# 5_Volts_and_3_3_Volts_Power_Supply.net
KiCad netlist of a schematic drawn in Altium Designer
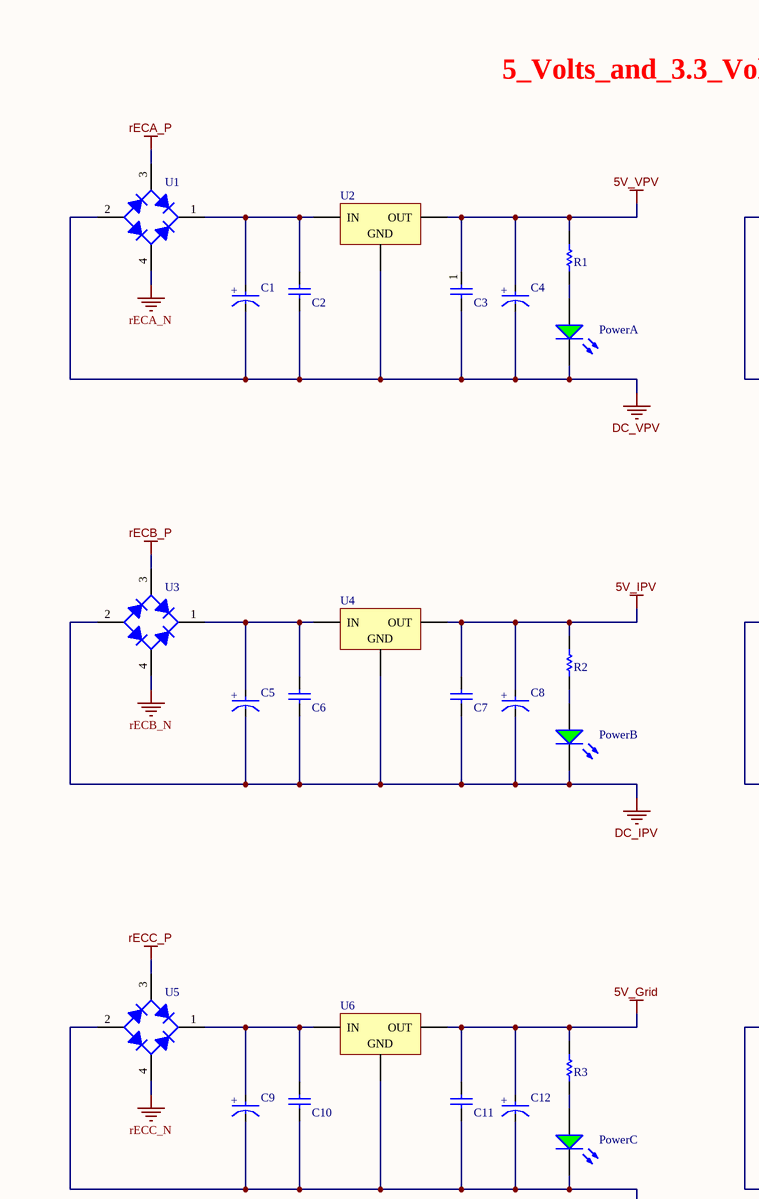
[diagram p0: 5_Volts_and_3.3_Volts_Power_Supply.SchDoc, top left]
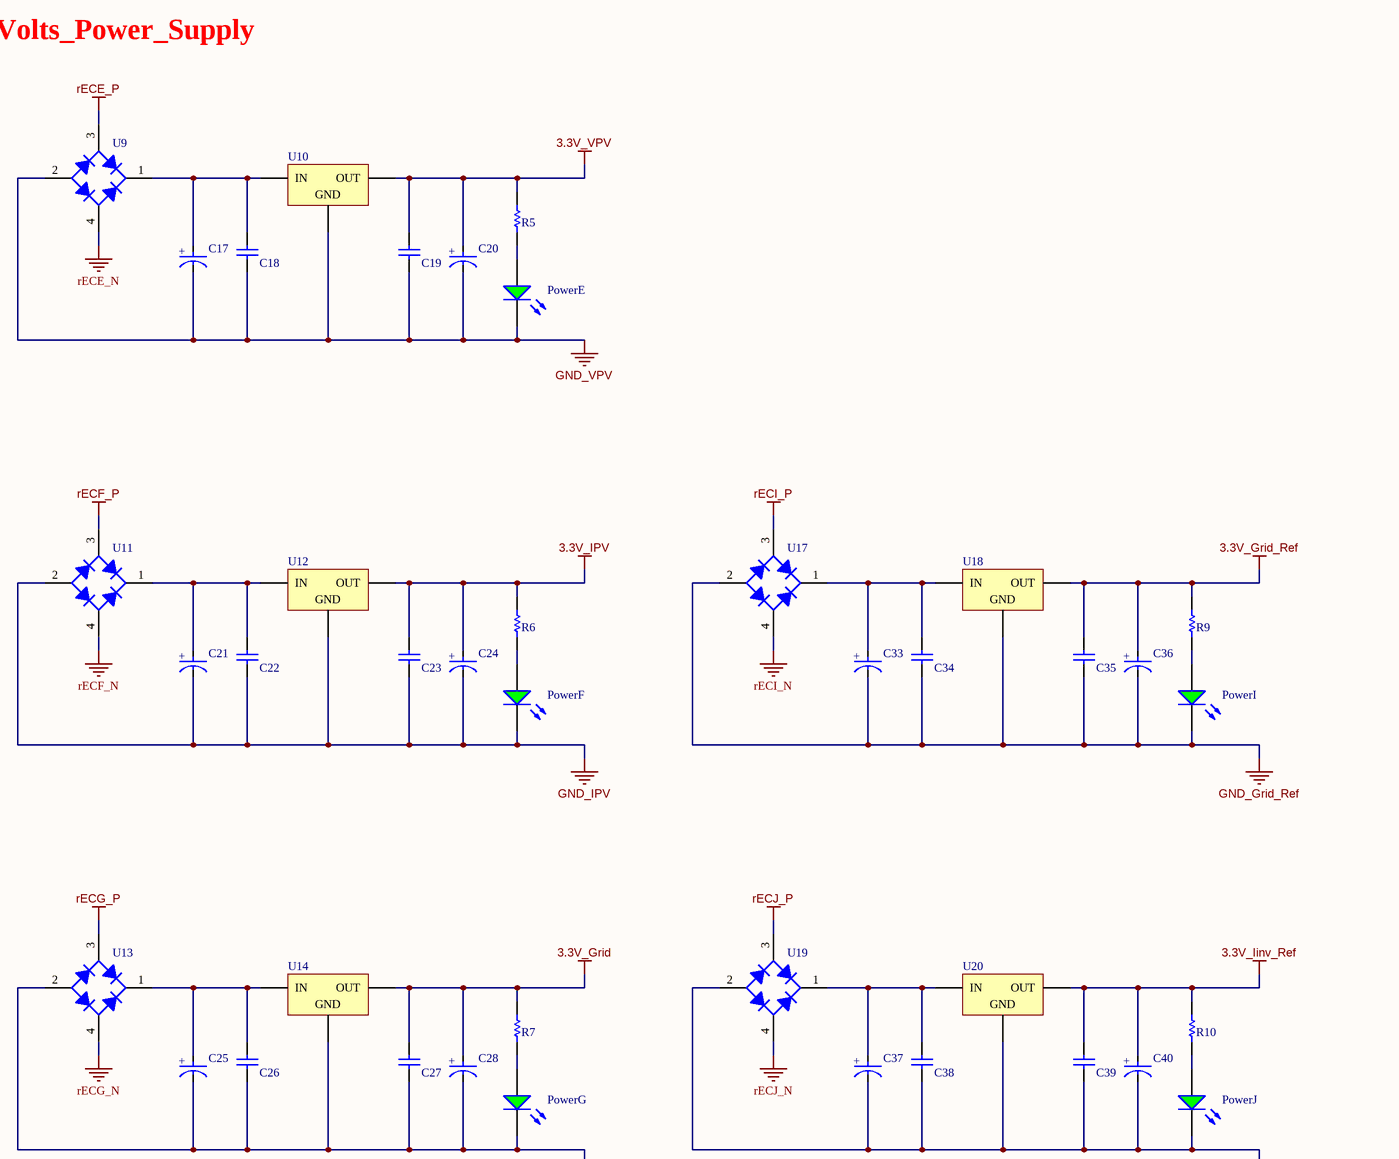
[diagram p1: 5_Volts_and_3.3_Volts_Power_Supply.SchDoc, top right]
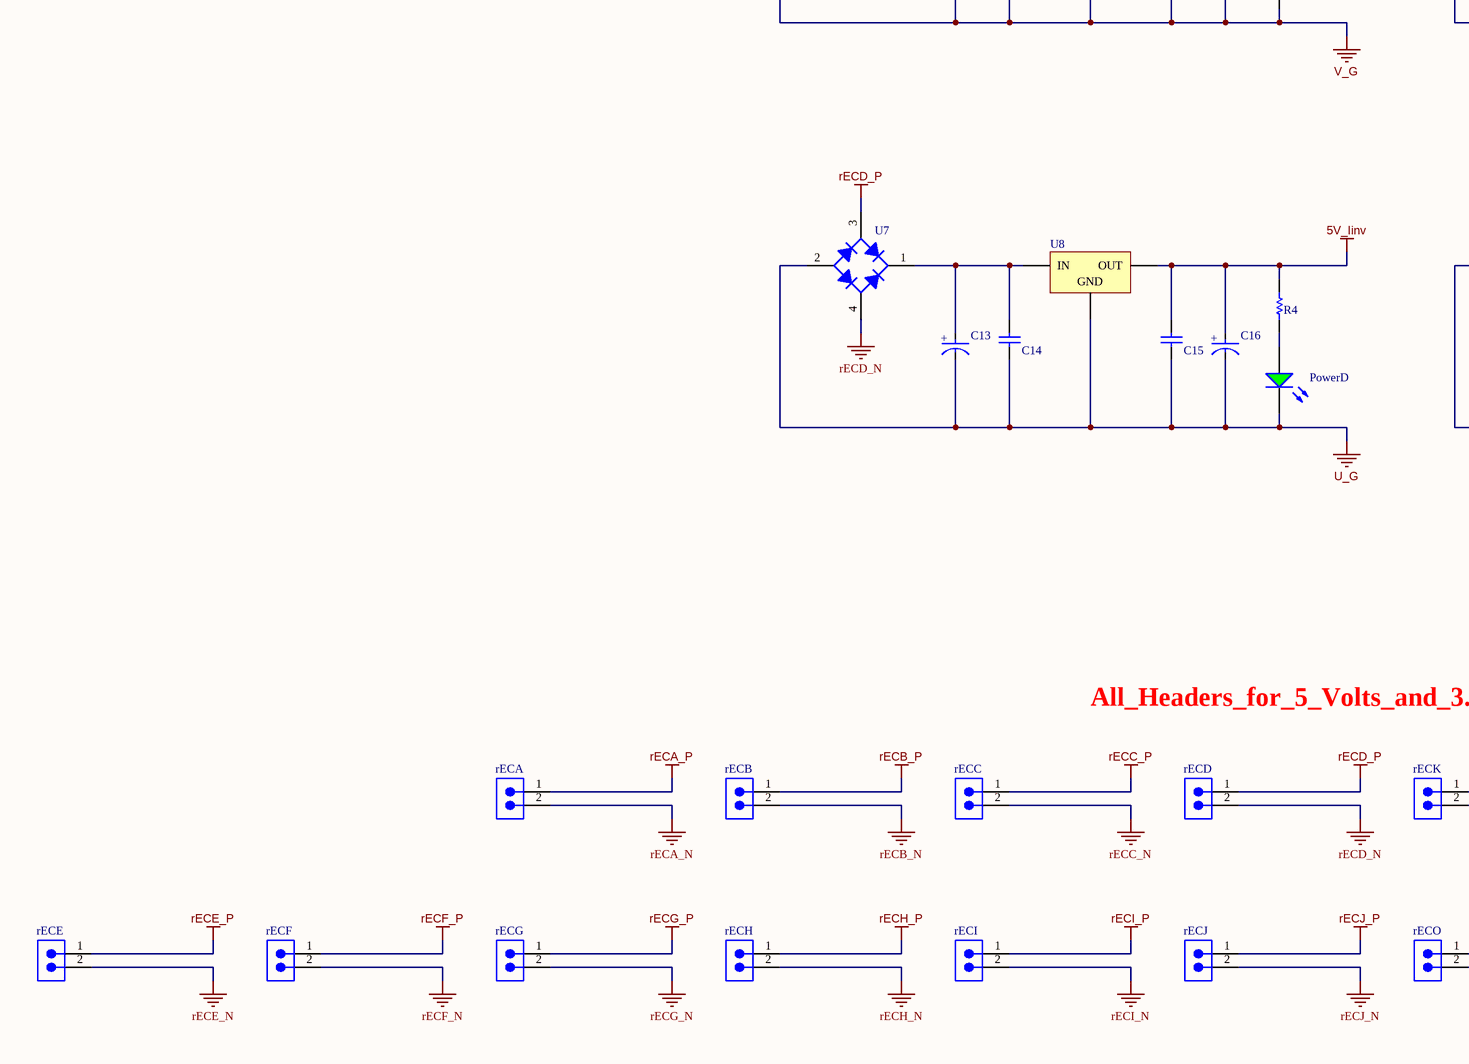
[diagram p2: 5_Volts_and_3.3_Volts_Power_Supply.SchDoc, bottom left]
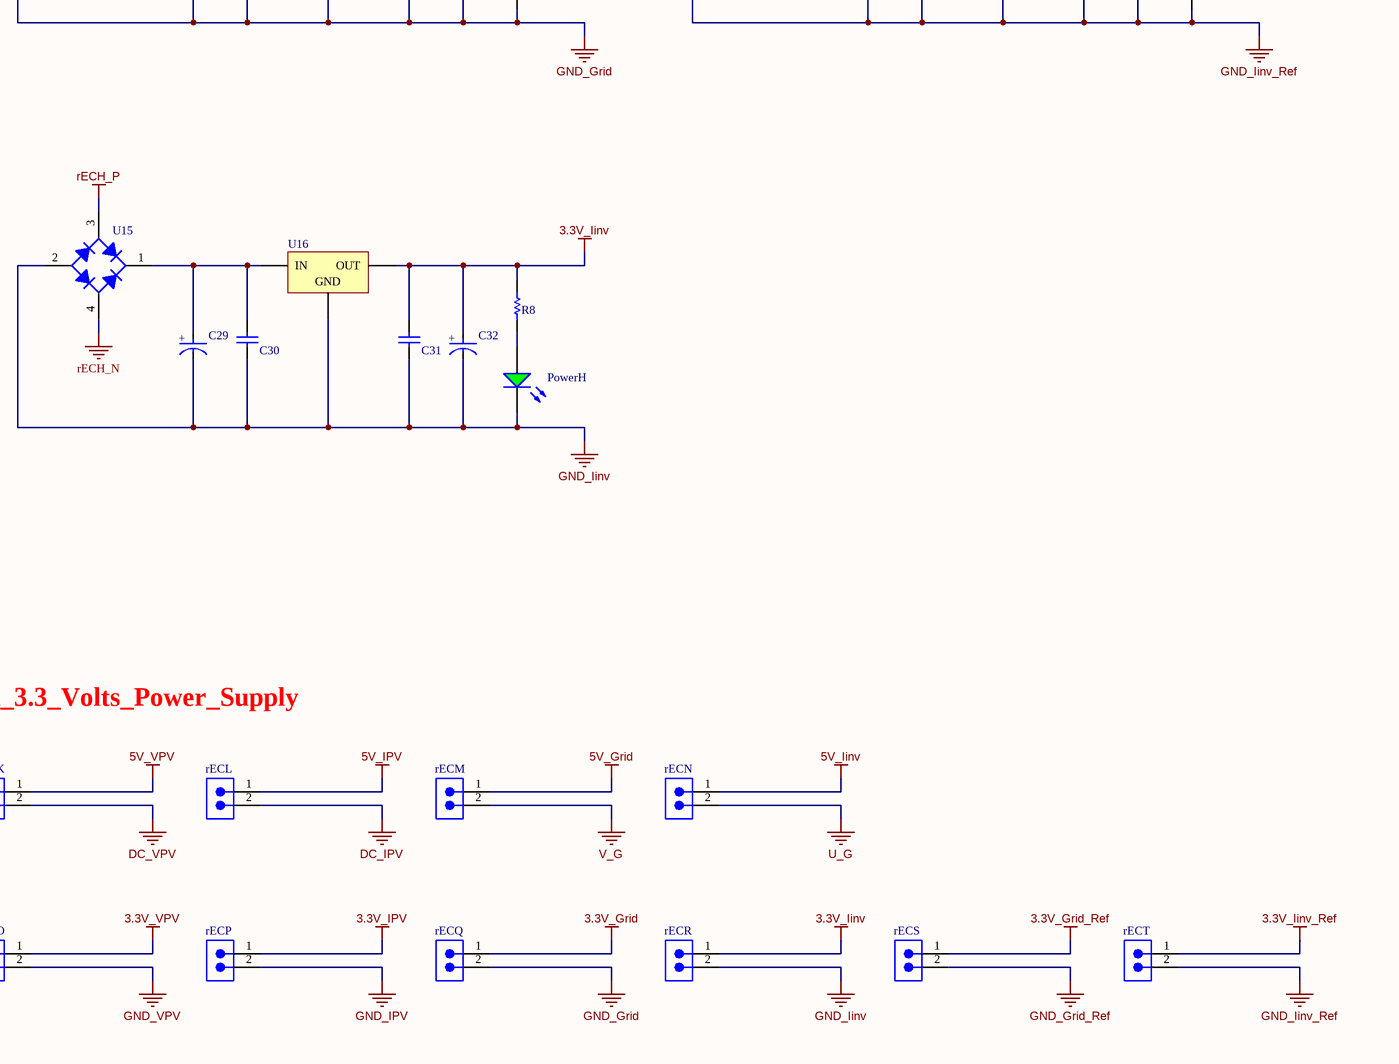
[diagram p3: 5_Volts_and_3.3_Volts_Power_Supply.SchDoc, bottom right]

(export (version "E")
  (design (tool "Eeschema 10.0.6"))
  (components
    (comp (ref "C1")
      (value "EEE-FK1H471AM")
      (footprint "FP-FKJ16-MFG")
      (description "CAP ALUM 470UF 20% 50V SMD")
      (fields (field (name "VOLTAGE") "50V") (field (name "TOLERANCE") "20%"))
      (libsource (lib "Altium Content Vault") (part "a00bbbee19879c290e62620ae7e47b1"))
    )
    (comp (ref "C2")
      (value "GRM219R71H334KA88D")
      (footprint "CAPC2013X95X45ML10T25")
      (description "Multilayer Ceramic Capacitor, 0.33 uF, 50 V, ï¿½ 10%, X7R, 0805 [2012 Metric]")
      (fields (field (name "MANUFACTURER") "Murata"))
      (libsource (lib "Altium Content Vault") (part "CAP"))
    )
    (comp (ref "C3")
      (value "GRM21BR71H104KA01L")
      (footprint "CAPC2013X135X45ML10T25")
      (description "Chip Capacitor, 0.1 uF, +/- 10%, 50 V, -55 to 125 degC, 0805 (2012 Metric), RoHS, Tape and Reel")
      (fields (field (name "VOLTAGE") "50V") (field (name "TOLERANCE") "10%"))
      (libsource (lib "") (part "CAP-NP-2_1"))
    )
    (comp (ref "C4")
      (value "EEE-FK1H100UR")
      (footprint "FP-FKC-MFG")
      (description "CAP ALUM 10UF 20% 50V SMD")
      (fields (field (name "TOLERANCE") "20%") (field (name "VOLTAGE") "50V"))
      (libsource (lib "Altium Content Vault") (part "a00bbbee19879c290e62620ae7e47b1"))
    )
    (comp (ref "C5")
      (value "EEE-FK1H471AM")
      (footprint "FP-FKJ16-MFG")
      (description "CAP ALUM 470UF 20% 50V SMD")
      (fields (field (name "VOLTAGE") "50V") (field (name "TOLERANCE") "20%"))
      (libsource (lib "Altium Content Vault") (part "a00bbbee19879c290e62620ae7e47b1"))
    )
    (comp (ref "C6")
      (value "GRM219R71H334KA88D")
      (footprint "CAPC2013X95X45ML10T25")
      (description "Multilayer Ceramic Capacitor, 0.33 uF, 50 V, ï¿½ 10%, X7R, 0805 [2012 Metric]")
      (fields (field (name "MANUFACTURER") "Murata"))
      (libsource (lib "Altium Content Vault") (part "CAP"))
    )
    (comp (ref "C7")
      (value "GRM21BR71H104KA01L")
      (footprint "CAPC2013X135X45ML10T25")
      (description "Chip Capacitor, 0.1 uF, +/- 10%, 50 V, -55 to 125 degC, 0805 (2012 Metric), RoHS, Tape and Reel")
      (fields (field (name "VOLTAGE") "50V") (field (name "TOLERANCE") "10%"))
      (libsource (lib "Altium Content Vault") (part "CAP-NP-2"))
    )
    (comp (ref "C8")
      (value "EEE-FK1H100UR")
      (footprint "FP-FKC-MFG")
      (description "CAP ALUM 10UF 20% 50V SMD")
      (fields (field (name "TOLERANCE") "20%") (field (name "VOLTAGE") "50V"))
      (libsource (lib "Altium Content Vault") (part "a00bbbee19879c290e62620ae7e47b1"))
    )
    (comp (ref "C9")
      (value "EEE-FK1H471AM")
      (footprint "FP-FKJ16-MFG")
      (description "CAP ALUM 470UF 20% 50V SMD")
      (fields (field (name "VOLTAGE") "50V") (field (name "TOLERANCE") "20%"))
      (libsource (lib "Altium Content Vault") (part "a00bbbee19879c290e62620ae7e47b1"))
    )
    (comp (ref "C10")
      (value "GRM219R71H334KA88D")
      (footprint "CAPC2013X95X45ML10T25")
      (description "Multilayer Ceramic Capacitor, 0.33 uF, 50 V, ï¿½ 10%, X7R, 0805 [2012 Metric]")
      (fields (field (name "MANUFACTURER") "Murata"))
      (libsource (lib "Altium Content Vault") (part "CAP"))
    )
    (comp (ref "C11")
      (value "GRM21BR71H104KA01L")
      (footprint "CAPC2013X135X45ML10T25")
      (description "Chip Capacitor, 0.1 uF, +/- 10%, 50 V, -55 to 125 degC, 0805 (2012 Metric), RoHS, Tape and Reel")
      (fields (field (name "VOLTAGE") "50V") (field (name "TOLERANCE") "10%"))
      (libsource (lib "Altium Content Vault") (part "CAP-NP-2"))
    )
    (comp (ref "C12")
      (value "EEE-FK1H100UR")
      (footprint "FP-FKC-MFG")
      (description "CAP ALUM 10UF 20% 50V SMD")
      (fields (field (name "TOLERANCE") "20%") (field (name "VOLTAGE") "50V"))
      (libsource (lib "Altium Content Vault") (part "a00bbbee19879c290e62620ae7e47b1"))
    )
    (comp (ref "C13")
      (value "EEE-FK1H471AM")
      (footprint "FP-FKJ16-MFG")
      (description "CAP ALUM 470UF 20% 50V SMD")
      (fields (field (name "VOLTAGE") "50V") (field (name "TOLERANCE") "20%"))
      (libsource (lib "Altium Content Vault") (part "a00bbbee19879c290e62620ae7e47b1"))
    )
    (comp (ref "C14")
      (value "GRM219R71H334KA88D")
      (footprint "CAPC2013X95X45ML10T25")
      (description "Multilayer Ceramic Capacitor, 0.33 uF, 50 V, ï¿½ 10%, X7R, 0805 [2012 Metric]")
      (fields (field (name "MANUFACTURER") "Murata"))
      (libsource (lib "Altium Content Vault") (part "CAP"))
    )
    (comp (ref "C15")
      (value "GRM21BR71H104KA01L")
      (footprint "CAPC2013X135X45ML10T25")
      (description "Chip Capacitor, 0.1 uF, +/- 10%, 50 V, -55 to 125 degC, 0805 (2012 Metric), RoHS, Tape and Reel")
      (fields (field (name "VOLTAGE") "50V") (field (name "TOLERANCE") "10%"))
      (libsource (lib "Altium Content Vault") (part "CAP-NP-2"))
    )
    (comp (ref "C16")
      (value "EEE-FK1H100UR")
      (footprint "FP-FKC-MFG")
      (description "CAP ALUM 10UF 20% 50V SMD")
      (fields (field (name "TOLERANCE") "20%") (field (name "VOLTAGE") "50V"))
      (libsource (lib "Altium Content Vault") (part "a00bbbee19879c290e62620ae7e47b1"))
    )
    (comp (ref "C17")
      (value "EEE-FK1H471AM")
      (footprint "FP-FKJ16-MFG")
      (description "CAP ALUM 470UF 20% 50V SMD")
      (fields (field (name "VOLTAGE") "50V") (field (name "TOLERANCE") "20%"))
      (libsource (lib "Altium Content Vault") (part "a00bbbee19879c290e62620ae7e47b1"))
    )
    (comp (ref "C18")
      (value "GRM219R71H334KA88D")
      (footprint "CAPC2013X95X45ML10T25")
      (description "Multilayer Ceramic Capacitor, 0.33 uF, 50 V, ï¿½ 10%, X7R, 0805 [2012 Metric]")
      (fields (field (name "MANUFACTURER") "Murata"))
      (libsource (lib "Altium Content Vault") (part "CAP"))
    )
    (comp (ref "C19")
      (value "GRM21BR71H104KA01L")
      (footprint "CAPC2013X135X45ML10T25")
      (description "Chip Capacitor, 0.1 uF, +/- 10%, 50 V, -55 to 125 degC, 0805 (2012 Metric), RoHS, Tape and Reel")
      (fields (field (name "VOLTAGE") "50V") (field (name "TOLERANCE") "10%"))
      (libsource (lib "Altium Content Vault") (part "CAP-NP-2"))
    )
    (comp (ref "C20")
      (value "EEE-FK1H100UR")
      (footprint "FP-FKC-MFG")
      (description "CAP ALUM 10UF 20% 50V SMD")
      (fields (field (name "TOLERANCE") "20%") (field (name "VOLTAGE") "50V"))
      (libsource (lib "Altium Content Vault") (part "a00bbbee19879c290e62620ae7e47b1"))
    )
    (comp (ref "C21")
      (value "EEE-FK1H471AM")
      (footprint "FP-FKJ16-MFG")
      (description "CAP ALUM 470UF 20% 50V SMD")
      (fields (field (name "VOLTAGE") "50V") (field (name "TOLERANCE") "20%"))
      (libsource (lib "Altium Content Vault") (part "a00bbbee19879c290e62620ae7e47b1"))
    )
    (comp (ref "C22")
      (value "GRM219R71H334KA88D")
      (footprint "CAPC2013X95X45ML10T25")
      (description "Multilayer Ceramic Capacitor, 0.33 uF, 50 V, ï¿½ 10%, X7R, 0805 [2012 Metric]")
      (fields (field (name "MANUFACTURER") "Murata"))
      (libsource (lib "Altium Content Vault") (part "CAP"))
    )
    (comp (ref "C23")
      (value "GRM21BR71H104KA01L")
      (footprint "CAPC2013X135X45ML10T25")
      (description "Chip Capacitor, 0.1 uF, +/- 10%, 50 V, -55 to 125 degC, 0805 (2012 Metric), RoHS, Tape and Reel")
      (fields (field (name "VOLTAGE") "50V") (field (name "TOLERANCE") "10%"))
      (libsource (lib "Altium Content Vault") (part "CAP-NP-2"))
    )
    (comp (ref "C24")
      (value "EEE-FK1H100UR")
      (footprint "FP-FKC-MFG")
      (description "CAP ALUM 10UF 20% 50V SMD")
      (fields (field (name "TOLERANCE") "20%") (field (name "VOLTAGE") "50V"))
      (libsource (lib "Altium Content Vault") (part "a00bbbee19879c290e62620ae7e47b1"))
    )
    (comp (ref "C25")
      (value "EEE-FK1H471AM")
      (footprint "FP-FKJ16-MFG")
      (description "CAP ALUM 470UF 20% 50V SMD")
      (fields (field (name "VOLTAGE") "50V") (field (name "TOLERANCE") "20%"))
      (libsource (lib "Altium Content Vault") (part "a00bbbee19879c290e62620ae7e47b1"))
    )
    (comp (ref "C26")
      (value "GRM219R71H334KA88D")
      (footprint "CAPC2013X95X45ML10T25")
      (description "Multilayer Ceramic Capacitor, 0.33 uF, 50 V, ï¿½ 10%, X7R, 0805 [2012 Metric]")
      (fields (field (name "MANUFACTURER") "Murata"))
      (libsource (lib "Altium Content Vault") (part "CAP"))
    )
    (comp (ref "C27")
      (value "GRM21BR71H104KA01L")
      (footprint "CAPC2013X135X45ML10T25")
      (description "Chip Capacitor, 0.1 uF, +/- 10%, 50 V, -55 to 125 degC, 0805 (2012 Metric), RoHS, Tape and Reel")
      (fields (field (name "VOLTAGE") "50V") (field (name "TOLERANCE") "10%"))
      (libsource (lib "Altium Content Vault") (part "CAP-NP-2"))
    )
    (comp (ref "C28")
      (value "EEE-FK1H100UR")
      (footprint "FP-FKC-MFG")
      (description "CAP ALUM 10UF 20% 50V SMD")
      (fields (field (name "TOLERANCE") "20%") (field (name "VOLTAGE") "50V"))
      (libsource (lib "Altium Content Vault") (part "a00bbbee19879c290e62620ae7e47b1"))
    )
    (comp (ref "C29")
      (value "EEE-FK1H471AM")
      (footprint "FP-FKJ16-MFG")
      (description "CAP ALUM 470UF 20% 50V SMD")
      (fields (field (name "VOLTAGE") "50V") (field (name "TOLERANCE") "20%"))
      (libsource (lib "Altium Content Vault") (part "a00bbbee19879c290e62620ae7e47b1"))
    )
    (comp (ref "C30")
      (value "GRM219R71H334KA88D")
      (footprint "CAPC2013X95X45ML10T25")
      (description "Multilayer Ceramic Capacitor, 0.33 uF, 50 V, ï¿½ 10%, X7R, 0805 [2012 Metric]")
      (fields (field (name "MANUFACTURER") "Murata"))
      (libsource (lib "Altium Content Vault") (part "CAP"))
    )
    (comp (ref "C31")
      (value "GRM21BR71H104KA01L")
      (footprint "CAPC2013X135X45ML10T25")
      (description "Chip Capacitor, 0.1 uF, +/- 10%, 50 V, -55 to 125 degC, 0805 (2012 Metric), RoHS, Tape and Reel")
      (fields (field (name "VOLTAGE") "50V") (field (name "TOLERANCE") "10%"))
      (libsource (lib "Altium Content Vault") (part "CAP-NP-2"))
    )
    (comp (ref "C32")
      (value "EEE-FK1H100UR")
      (footprint "FP-FKC-MFG")
      (description "CAP ALUM 10UF 20% 50V SMD")
      (fields (field (name "TOLERANCE") "20%") (field (name "VOLTAGE") "50V"))
      (libsource (lib "Altium Content Vault") (part "a00bbbee19879c290e62620ae7e47b1"))
    )
    (comp (ref "C33")
      (value "EEE-FK1H471AM")
      (footprint "FP-FKJ16-MFG")
      (description "CAP ALUM 470UF 20% 50V SMD")
      (fields (field (name "VOLTAGE") "50V") (field (name "TOLERANCE") "20%"))
      (libsource (lib "Altium Content Vault") (part "a00bbbee19879c290e62620ae7e47b1"))
    )
    (comp (ref "C34")
      (value "GRM219R71H334KA88D")
      (footprint "CAPC2013X95X45ML10T25")
      (description "Multilayer Ceramic Capacitor, 0.33 uF, 50 V, ï¿½ 10%, X7R, 0805 [2012 Metric]")
      (fields (field (name "MANUFACTURER") "Murata"))
      (libsource (lib "Altium Content Vault") (part "CAP"))
    )
    (comp (ref "C35")
      (value "GRM21BR71H104KA01L")
      (footprint "CAPC2013X135X45ML10T25")
      (description "Chip Capacitor, 0.1 uF, +/- 10%, 50 V, -55 to 125 degC, 0805 (2012 Metric), RoHS, Tape and Reel")
      (fields (field (name "VOLTAGE") "50V") (field (name "TOLERANCE") "10%"))
      (libsource (lib "Altium Content Vault") (part "CAP-NP-2"))
    )
    (comp (ref "C36")
      (value "EEE-FK1H100UR")
      (footprint "FP-FKC-MFG")
      (description "CAP ALUM 10UF 20% 50V SMD")
      (fields (field (name "TOLERANCE") "20%") (field (name "VOLTAGE") "50V"))
      (libsource (lib "Altium Content Vault") (part "a00bbbee19879c290e62620ae7e47b1"))
    )
    (comp (ref "C37")
      (value "EEE-FK1H471AM")
      (footprint "FP-FKJ16-MFG")
      (description "CAP ALUM 470UF 20% 50V SMD")
      (fields (field (name "VOLTAGE") "50V") (field (name "TOLERANCE") "20%"))
      (libsource (lib "Altium Content Vault") (part "a00bbbee19879c290e62620ae7e47b1"))
    )
    (comp (ref "C38")
      (value "GRM219R71H334KA88D")
      (footprint "CAPC2013X95X45ML10T25")
      (description "Multilayer Ceramic Capacitor, 0.33 uF, 50 V, ï¿½ 10%, X7R, 0805 [2012 Metric]")
      (fields (field (name "MANUFACTURER") "Murata"))
      (libsource (lib "Altium Content Vault") (part "CAP"))
    )
    (comp (ref "C39")
      (value "GRM21BR71H104KA01L")
      (footprint "CAPC2013X135X45ML10T25")
      (description "Chip Capacitor, 0.1 uF, +/- 10%, 50 V, -55 to 125 degC, 0805 (2012 Metric), RoHS, Tape and Reel")
      (fields (field (name "VOLTAGE") "50V") (field (name "TOLERANCE") "10%"))
      (libsource (lib "Altium Content Vault") (part "CAP-NP-2"))
    )
    (comp (ref "C40")
      (value "EEE-FK1H100UR")
      (footprint "FP-FKC-MFG")
      (description "CAP ALUM 10UF 20% 50V SMD")
      (fields (field (name "TOLERANCE") "20%") (field (name "VOLTAGE") "50V"))
      (libsource (lib "Altium Content Vault") (part "a00bbbee19879c290e62620ae7e47b1"))
    )
    (comp (ref "PowerA")
      (value "150080GS75000")
      (footprint "WL-SMCW_0805_150080xx75000")
      (description "WURTH ELEKTRONIK - 150080GS75000 - LED, Green, SMD, 0805, 30 mA, 3.2 V, 520 nm")
      (libsource (lib "Altium Content Vault") (part "LED_Green_2A-1K"))
    )
    (comp (ref "PowerB")
      (value "150080GS75000")
      (footprint "WL-SMCW_0805_150080xx75000")
      (description "WURTH ELEKTRONIK - 150080GS75000 - LED, Green, SMD, 0805, 30 mA, 3.2 V, 520 nm")
      (libsource (lib "Altium Content Vault") (part "LED_Green_2A-1K"))
    )
    (comp (ref "PowerC")
      (value "150080GS75000")
      (footprint "WL-SMCW_0805_150080xx75000")
      (description "WURTH ELEKTRONIK - 150080GS75000 - LED, Green, SMD, 0805, 30 mA, 3.2 V, 520 nm")
      (libsource (lib "Altium Content Vault") (part "LED_Green_2A-1K"))
    )
    (comp (ref "PowerD")
      (value "150080GS75000")
      (footprint "WL-SMCW_0805_150080xx75000")
      (description "WURTH ELEKTRONIK - 150080GS75000 - LED, Green, SMD, 0805, 30 mA, 3.2 V, 520 nm")
      (libsource (lib "Altium Content Vault") (part "LED_Green_2A-1K"))
    )
    (comp (ref "PowerE")
      (value "150080GS75000")
      (footprint "WL-SMCW_0805_150080xx75000")
      (description "WURTH ELEKTRONIK - 150080GS75000 - LED, Green, SMD, 0805, 30 mA, 3.2 V, 520 nm")
      (libsource (lib "Altium Content Vault") (part "LED_Green_2A-1K"))
    )
    (comp (ref "PowerF")
      (value "150080GS75000")
      (footprint "WL-SMCW_0805_150080xx75000")
      (description "WURTH ELEKTRONIK - 150080GS75000 - LED, Green, SMD, 0805, 30 mA, 3.2 V, 520 nm")
      (libsource (lib "Altium Content Vault") (part "LED_Green_2A-1K"))
    )
    (comp (ref "PowerG")
      (value "150080GS75000")
      (footprint "WL-SMCW_0805_150080xx75000")
      (description "WURTH ELEKTRONIK - 150080GS75000 - LED, Green, SMD, 0805, 30 mA, 3.2 V, 520 nm")
      (libsource (lib "Altium Content Vault") (part "LED_Green_2A-1K"))
    )
    (comp (ref "PowerH")
      (value "150080GS75000")
      (footprint "WL-SMCW_0805_150080xx75000")
      (description "WURTH ELEKTRONIK - 150080GS75000 - LED, Green, SMD, 0805, 30 mA, 3.2 V, 520 nm")
      (libsource (lib "Altium Content Vault") (part "LED_Green_2A-1K"))
    )
    (comp (ref "PowerI")
      (value "150080GS75000")
      (footprint "WL-SMCW_0805_150080xx75000")
      (description "WURTH ELEKTRONIK - 150080GS75000 - LED, Green, SMD, 0805, 30 mA, 3.2 V, 520 nm")
      (libsource (lib "Altium Content Vault") (part "LED_Green_2A-1K"))
    )
    (comp (ref "PowerJ")
      (value "150080GS75000")
      (footprint "WL-SMCW_0805_150080xx75000")
      (description "WURTH ELEKTRONIK - 150080GS75000 - LED, Green, SMD, 0805, 30 mA, 3.2 V, 520 nm")
      (libsource (lib "Altium Content Vault") (part "LED_Green_2A-1K"))
    )
    (comp (ref "R1")
      (value "ERJ-6ENF1001V")
      (footprint "RESC2013X70X40ML20T20")
      (description "Chip Resistor, 1 KOhm, +/- 1%, 0.125 W, -55 to 155 degC, 0805 (2012 Metric), RoHS, Tape and Reel")
      (fields (field (name "MANUFACTURER") "Panasonic"))
      (libsource (lib "Altium Content Vault") (part "RES-2"))
    )
    (comp (ref "R2")
      (value "ERJ-6ENF1001V")
      (footprint "RESC2013X70X40ML20T20")
      (description "Chip Resistor, 1 KOhm, +/- 1%, 0.125 W, -55 to 155 degC, 0805 (2012 Metric), RoHS, Tape and Reel")
      (fields (field (name "MANUFACTURER") "Panasonic"))
      (libsource (lib "Altium Content Vault") (part "RES-2"))
    )
    (comp (ref "R3")
      (value "ERJ-6ENF1001V")
      (footprint "RESC2013X70X40ML20T20")
      (description "Chip Resistor, 1 KOhm, +/- 1%, 0.125 W, -55 to 155 degC, 0805 (2012 Metric), RoHS, Tape and Reel")
      (fields (field (name "MANUFACTURER") "Panasonic"))
      (libsource (lib "Altium Content Vault") (part "RES-2"))
    )
    (comp (ref "R4")
      (value "ERJ-6ENF1001V")
      (footprint "RESC2013X70X40ML20T20")
      (description "Chip Resistor, 1 KOhm, +/- 1%, 0.125 W, -55 to 155 degC, 0805 (2012 Metric), RoHS, Tape and Reel")
      (fields (field (name "MANUFACTURER") "Panasonic"))
      (libsource (lib "Altium Content Vault") (part "RES-2"))
    )
    (comp (ref "R5")
      (value "ERJ-6ENF1001V")
      (footprint "RESC2013X70X40ML20T20")
      (description "Chip Resistor, 1 KOhm, +/- 1%, 0.125 W, -55 to 155 degC, 0805 (2012 Metric), RoHS, Tape and Reel")
      (fields (field (name "MANUFACTURER") "Panasonic"))
      (libsource (lib "Altium Content Vault") (part "RES-2"))
    )
    (comp (ref "R6")
      (value "ERJ-6ENF1001V")
      (footprint "RESC2013X70X40ML20T20")
      (description "Chip Resistor, 1 KOhm, +/- 1%, 0.125 W, -55 to 155 degC, 0805 (2012 Metric), RoHS, Tape and Reel")
      (fields (field (name "MANUFACTURER") "Panasonic"))
      (libsource (lib "Altium Content Vault") (part "RES-2"))
    )
    (comp (ref "R7")
      (value "ERJ-6ENF1001V")
      (footprint "RESC2013X70X40ML20T20")
      (description "Chip Resistor, 1 KOhm, +/- 1%, 0.125 W, -55 to 155 degC, 0805 (2012 Metric), RoHS, Tape and Reel")
      (fields (field (name "MANUFACTURER") "Panasonic"))
      (libsource (lib "Altium Content Vault") (part "RES-2"))
    )
    (comp (ref "R8")
      (value "ERJ-6ENF1001V")
      (footprint "RESC2013X70X40ML20T20")
      (description "Chip Resistor, 1 KOhm, +/- 1%, 0.125 W, -55 to 155 degC, 0805 (2012 Metric), RoHS, Tape and Reel")
      (fields (field (name "MANUFACTURER") "Panasonic"))
      (libsource (lib "Altium Content Vault") (part "RES-2"))
    )
    (comp (ref "R9")
      (value "ERJ-6ENF1001V")
      (footprint "RESC2013X70X40ML20T20")
      (description "Chip Resistor, 1 KOhm, +/- 1%, 0.125 W, -55 to 155 degC, 0805 (2012 Metric), RoHS, Tape and Reel")
      (fields (field (name "MANUFACTURER") "Panasonic"))
      (libsource (lib "Altium Content Vault") (part "RES-2"))
    )
    (comp (ref "R10")
      (value "ERJ-6ENF1001V")
      (footprint "RESC2013X70X40ML20T20")
      (description "Chip Resistor, 1 KOhm, +/- 1%, 0.125 W, -55 to 155 degC, 0805 (2012 Metric), RoHS, Tape and Reel")
      (fields (field (name "MANUFACTURER") "Panasonic"))
      (libsource (lib "Altium Content Vault") (part "RES-2"))
    )
    (comp (ref "rECA")
      (value "61900211121")
      (footprint "61900211121")
      (description "2 Position 2.54mm Pitch Vertical ThroughHole Non-Shrouded Header")
      (libsource (lib "Altium Content Vault") (part "Header_Male_1R_02P"))
    )
    (comp (ref "rECB")
      (value "61900211121")
      (footprint "61900211121")
      (description "2 Position 2.54mm Pitch Vertical ThroughHole Non-Shrouded Header")
      (libsource (lib "Altium Content Vault") (part "Header_Male_1R_02P"))
    )
    (comp (ref "rECC")
      (value "61900211121")
      (footprint "61900211121")
      (description "2 Position 2.54mm Pitch Vertical ThroughHole Non-Shrouded Header")
      (libsource (lib "Altium Content Vault") (part "Header_Male_1R_02P"))
    )
    (comp (ref "rECD")
      (value "61900211121")
      (footprint "61900211121")
      (description "2 Position 2.54mm Pitch Vertical ThroughHole Non-Shrouded Header")
      (libsource (lib "Altium Content Vault") (part "Header_Male_1R_02P"))
    )
    (comp (ref "rECE")
      (value "61900211121")
      (footprint "61900211121")
      (description "2 Position 2.54mm Pitch Vertical ThroughHole Non-Shrouded Header")
      (libsource (lib "Altium Content Vault") (part "Header_Male_1R_02P"))
    )
    (comp (ref "rECF")
      (value "61900211121")
      (footprint "61900211121")
      (description "2 Position 2.54mm Pitch Vertical ThroughHole Non-Shrouded Header")
      (libsource (lib "Altium Content Vault") (part "Header_Male_1R_02P"))
    )
    (comp (ref "rECG")
      (value "61900211121")
      (footprint "61900211121")
      (description "2 Position 2.54mm Pitch Vertical ThroughHole Non-Shrouded Header")
      (libsource (lib "Altium Content Vault") (part "Header_Male_1R_02P"))
    )
    (comp (ref "rECH")
      (value "61900211121")
      (footprint "61900211121")
      (description "2 Position 2.54mm Pitch Vertical ThroughHole Non-Shrouded Header")
      (libsource (lib "Altium Content Vault") (part "Header_Male_1R_02P"))
    )
    (comp (ref "rECI")
      (value "61900211121")
      (footprint "61900211121")
      (description "2 Position 2.54mm Pitch Vertical ThroughHole Non-Shrouded Header")
      (libsource (lib "Altium Content Vault") (part "Header_Male_1R_02P"))
    )
    (comp (ref "rECJ")
      (value "61900211121")
      (footprint "61900211121")
      (description "2 Position 2.54mm Pitch Vertical ThroughHole Non-Shrouded Header")
      (libsource (lib "Altium Content Vault") (part "Header_Male_1R_02P"))
    )
    (comp (ref "rECK")
      (value "61900211121")
      (footprint "61900211121")
      (description "2 Position 2.54mm Pitch Vertical ThroughHole Non-Shrouded Header")
      (libsource (lib "Altium Content Vault") (part "Header_Male_1R_02P"))
    )
    (comp (ref "rECL")
      (value "61900211121")
      (footprint "61900211121")
      (description "2 Position 2.54mm Pitch Vertical ThroughHole Non-Shrouded Header")
      (libsource (lib "Altium Content Vault") (part "Header_Male_1R_02P"))
    )
    (comp (ref "rECM")
      (value "61900211121")
      (footprint "61900211121")
      (description "2 Position 2.54mm Pitch Vertical ThroughHole Non-Shrouded Header")
      (libsource (lib "Altium Content Vault") (part "Header_Male_1R_02P"))
    )
    (comp (ref "rECN")
      (value "61900211121")
      (footprint "61900211121")
      (description "2 Position 2.54mm Pitch Vertical ThroughHole Non-Shrouded Header")
      (libsource (lib "Altium Content Vault") (part "Header_Male_1R_02P"))
    )
    (comp (ref "rECO")
      (value "61900211121")
      (footprint "61900211121")
      (description "2 Position 2.54mm Pitch Vertical ThroughHole Non-Shrouded Header")
      (libsource (lib "Altium Content Vault") (part "Header_Male_1R_02P"))
    )
    (comp (ref "rECP")
      (value "61900211121")
      (footprint "61900211121")
      (description "2 Position 2.54mm Pitch Vertical ThroughHole Non-Shrouded Header")
      (libsource (lib "Altium Content Vault") (part "Header_Male_1R_02P"))
    )
    (comp (ref "rECQ")
      (value "61900211121")
      (footprint "61900211121")
      (description "2 Position 2.54mm Pitch Vertical ThroughHole Non-Shrouded Header")
      (libsource (lib "Altium Content Vault") (part "Header_Male_1R_02P"))
    )
    (comp (ref "rECR")
      (value "61900211121")
      (footprint "61900211121")
      (description "2 Position 2.54mm Pitch Vertical ThroughHole Non-Shrouded Header")
      (libsource (lib "Altium Content Vault") (part "Header_Male_1R_02P"))
    )
    (comp (ref "rECS")
      (value "61900211121")
      (footprint "61900211121")
      (description "2 Position 2.54mm Pitch Vertical ThroughHole Non-Shrouded Header")
      (libsource (lib "Altium Content Vault") (part "Header_Male_1R_02P"))
    )
    (comp (ref "rECT")
      (value "61900211121")
      (footprint "61900211121")
      (description "2 Position 2.54mm Pitch Vertical ThroughHole Non-Shrouded Header")
      (libsource (lib "Altium Content Vault") (part "Header_Male_1R_02P"))
    )
    (comp (ref "U1")
      (value "DF10S")
      (footprint "FAIR-SDIP-4_V")
      (description "Bridge Rectifier, 1.5 A, 1000 V, 4-Pin SDIP, RoHS, Tape and Reel")
      (fields (field (name "MANUFACTURER") "FairchildSemiconductor"))
      (libsource (lib "Altium Content Vault") (part "D-KACC-4"))
    )
    (comp (ref "U2")
      (value "L78M05CDT-TR")
      (footprint "TO-252_L")
      (description "Positive Voltage Regulator, 5V, 3-Pin DPAK, Tape and Reel")
      (libsource (lib "Altium Content Vault") (part "PM-REG-L4940-SOT3"))
    )
    (comp (ref "U3")
      (value "DF10S")
      (footprint "FAIR-SDIP-4_V")
      (description "Bridge Rectifier, 1.5 A, 1000 V, 4-Pin SDIP, RoHS, Tape and Reel")
      (fields (field (name "MANUFACTURER") "FairchildSemiconductor"))
      (libsource (lib "Altium Content Vault") (part "D-KACC-4"))
    )
    (comp (ref "U4")
      (value "L78M05CDT-TR")
      (footprint "TO-252_L")
      (description "Positive Voltage Regulator, 5V, 3-Pin DPAK, Tape and Reel")
      (libsource (lib "Altium Content Vault") (part "PM-REG-L4940-SOT3"))
    )
    (comp (ref "U5")
      (value "DF10S")
      (footprint "FAIR-SDIP-4_V")
      (description "Bridge Rectifier, 1.5 A, 1000 V, 4-Pin SDIP, RoHS, Tape and Reel")
      (fields (field (name "MANUFACTURER") "FairchildSemiconductor"))
      (libsource (lib "Altium Content Vault") (part "D-KACC-4"))
    )
    (comp (ref "U6")
      (value "L78M05CDT-TR")
      (footprint "TO-252_L")
      (description "Positive Voltage Regulator, 5V, 3-Pin DPAK, Tape and Reel")
      (libsource (lib "Altium Content Vault") (part "PM-REG-L4940-SOT3"))
    )
    (comp (ref "U7")
      (value "DF10S")
      (footprint "FAIR-SDIP-4_V")
      (description "Bridge Rectifier, 1.5 A, 1000 V, 4-Pin SDIP, RoHS, Tape and Reel")
      (fields (field (name "MANUFACTURER") "FairchildSemiconductor"))
      (libsource (lib "Altium Content Vault") (part "D-KACC-4"))
    )
    (comp (ref "U8")
      (value "L78M05CDT-TR")
      (footprint "TO-252_L")
      (description "Positive Voltage Regulator, 5V, 3-Pin DPAK, Tape and Reel")
      (libsource (lib "Altium Content Vault") (part "PM-REG-L4940-SOT3"))
    )
    (comp (ref "U9")
      (value "DF10S")
      (footprint "FAIR-SDIP-4_V")
      (description "Bridge Rectifier, 1.5 A, 1000 V, 4-Pin SDIP, RoHS, Tape and Reel")
      (fields (field (name "MANUFACTURER") "FairchildSemiconductor"))
      (libsource (lib "Altium Content Vault") (part "D-KACC-4"))
    )
    (comp (ref "U10")
      (value "LF33ABDT-TR")
      (footprint "TO-252_N")
      (description "500mA, Very Low Drop (0.45V) Voltage Regulator, 3.3V, 3-Pin DPAK, Tape and Reel")
      (libsource (lib "Altium Content Vault") (part "PM-REG-L4940-SOT3"))
    )
    (comp (ref "U11")
      (value "DF10S")
      (footprint "FAIR-SDIP-4_V")
      (description "Bridge Rectifier, 1.5 A, 1000 V, 4-Pin SDIP, RoHS, Tape and Reel")
      (fields (field (name "MANUFACTURER") "FairchildSemiconductor"))
      (libsource (lib "Altium Content Vault") (part "D-KACC-4"))
    )
    (comp (ref "U12")
      (value "LF33ABDT-TR")
      (footprint "TO-252_N")
      (description "500mA, Very Low Drop (0.45V) Voltage Regulator, 3.3V, 3-Pin DPAK, Tape and Reel")
      (libsource (lib "Altium Content Vault") (part "PM-REG-L4940-SOT3"))
    )
    (comp (ref "U13")
      (value "DF10S")
      (footprint "FAIR-SDIP-4_V")
      (description "Bridge Rectifier, 1.5 A, 1000 V, 4-Pin SDIP, RoHS, Tape and Reel")
      (fields (field (name "MANUFACTURER") "FairchildSemiconductor"))
      (libsource (lib "Altium Content Vault") (part "D-KACC-4"))
    )
    (comp (ref "U14")
      (value "LF33ABDT-TR")
      (footprint "TO-252_N")
      (description "500mA, Very Low Drop (0.45V) Voltage Regulator, 3.3V, 3-Pin DPAK, Tape and Reel")
      (libsource (lib "Altium Content Vault") (part "PM-REG-L4940-SOT3"))
    )
    (comp (ref "U15")
      (value "DF10S")
      (footprint "FAIR-SDIP-4_V")
      (description "Bridge Rectifier, 1.5 A, 1000 V, 4-Pin SDIP, RoHS, Tape and Reel")
      (fields (field (name "MANUFACTURER") "FairchildSemiconductor"))
      (libsource (lib "Altium Content Vault") (part "D-KACC-4"))
    )
    (comp (ref "U16")
      (value "LF33ABDT-TR")
      (footprint "TO-252_N")
      (description "500mA, Very Low Drop (0.45V) Voltage Regulator, 3.3V, 3-Pin DPAK, Tape and Reel")
      (libsource (lib "Altium Content Vault") (part "PM-REG-L4940-SOT3"))
    )
    (comp (ref "U17")
      (value "DF10S")
      (footprint "FAIR-SDIP-4_V")
      (description "Bridge Rectifier, 1.5 A, 1000 V, 4-Pin SDIP, RoHS, Tape and Reel")
      (fields (field (name "MANUFACTURER") "FairchildSemiconductor"))
      (libsource (lib "Altium Content Vault") (part "D-KACC-4"))
    )
    (comp (ref "U18")
      (value "LF33ABDT-TR")
      (footprint "TO-252_N")
      (description "500mA, Very Low Drop (0.45V) Voltage Regulator, 3.3V, 3-Pin DPAK, Tape and Reel")
      (libsource (lib "Altium Content Vault") (part "PM-REG-L4940-SOT3"))
    )
    (comp (ref "U19")
      (value "DF10S")
      (footprint "FAIR-SDIP-4_V")
      (description "Bridge Rectifier, 1.5 A, 1000 V, 4-Pin SDIP, RoHS, Tape and Reel")
      (fields (field (name "MANUFACTURER") "FairchildSemiconductor"))
      (libsource (lib "Altium Content Vault") (part "D-KACC-4"))
    )
    (comp (ref "U20")
      (value "LF33ABDT-TR")
      (footprint "TO-252_N")
      (description "500mA, Very Low Drop (0.45V) Voltage Regulator, 3.3V, 3-Pin DPAK, Tape and Reel")
      (libsource (lib "Altium Content Vault") (part "PM-REG-L4940-SOT3"))
    )
  )
  (nets
    (net (code "1") (name "3.3V_Grid") (class "Default")
      (node (ref "C27") (pin "1") (pinfunction "1_1") (pintype "passive"))
      (node (ref "C28") (pin "2") (pinfunction "A_2") (pintype "passive"))
      (node (ref "R7") (pin "1") (pinfunction "1_1") (pintype "passive"))
      (node (ref "U14") (pin "3") (pinfunction "OUT_3") (pintype "power_in"))
      (node (ref "rECQ") (pin "1") (pinfunction "1_1") (pintype "passive"))
    )
    (net (code "2") (name "3.3V_Grid_Ref") (class "Default")
      (node (ref "C35") (pin "1") (pinfunction "1_1") (pintype "passive"))
      (node (ref "C36") (pin "2") (pinfunction "A_2") (pintype "passive"))
      (node (ref "R9") (pin "1") (pinfunction "1_1") (pintype "passive"))
      (node (ref "U18") (pin "3") (pinfunction "OUT_3") (pintype "power_in"))
      (node (ref "rECS") (pin "1") (pinfunction "1_1") (pintype "passive"))
    )
    (net (code "3") (name "3.3V_IPV") (class "Default")
      (node (ref "C23") (pin "1") (pinfunction "1_1") (pintype "passive"))
      (node (ref "C24") (pin "2") (pinfunction "A_2") (pintype "passive"))
      (node (ref "R6") (pin "1") (pinfunction "1_1") (pintype "passive"))
      (node (ref "U12") (pin "3") (pinfunction "OUT_3") (pintype "power_in"))
      (node (ref "rECP") (pin "1") (pinfunction "1_1") (pintype "passive"))
    )
    (net (code "4") (name "3.3V_Iinv") (class "Default")
      (node (ref "C31") (pin "1") (pinfunction "1_1") (pintype "passive"))
      (node (ref "C32") (pin "2") (pinfunction "A_2") (pintype "passive"))
      (node (ref "R8") (pin "1") (pinfunction "1_1") (pintype "passive"))
      (node (ref "U16") (pin "3") (pinfunction "OUT_3") (pintype "power_in"))
      (node (ref "rECR") (pin "1") (pinfunction "1_1") (pintype "passive"))
    )
    (net (code "5") (name "3.3V_Iinv_Ref") (class "Default")
      (node (ref "C39") (pin "1") (pinfunction "1_1") (pintype "passive"))
      (node (ref "C40") (pin "2") (pinfunction "A_2") (pintype "passive"))
      (node (ref "R10") (pin "1") (pinfunction "1_1") (pintype "passive"))
      (node (ref "U20") (pin "3") (pinfunction "OUT_3") (pintype "power_in"))
      (node (ref "rECT") (pin "1") (pinfunction "1_1") (pintype "passive"))
    )
    (net (code "6") (name "3.3V_VPV") (class "Default")
      (node (ref "C19") (pin "1") (pinfunction "1_1") (pintype "passive"))
      (node (ref "C20") (pin "2") (pinfunction "A_2") (pintype "passive"))
      (node (ref "R5") (pin "1") (pinfunction "1_1") (pintype "passive"))
      (node (ref "U10") (pin "3") (pinfunction "OUT_3") (pintype "power_in"))
      (node (ref "rECO") (pin "1") (pinfunction "1_1") (pintype "passive"))
    )
    (net (code "7") (name "5V_Grid") (class "Default")
      (node (ref "C11") (pin "1") (pinfunction "1_1") (pintype "passive"))
      (node (ref "C12") (pin "2") (pinfunction "A_2") (pintype "passive"))
      (node (ref "R3") (pin "1") (pinfunction "1_1") (pintype "passive"))
      (node (ref "U6") (pin "3") (pinfunction "OUT_3") (pintype "power_in"))
      (node (ref "rECM") (pin "1") (pinfunction "1_1") (pintype "passive"))
    )
    (net (code "8") (name "5V_IPV") (class "Default")
      (node (ref "C7") (pin "1") (pinfunction "1_1") (pintype "passive"))
      (node (ref "C8") (pin "2") (pinfunction "A_2") (pintype "passive"))
      (node (ref "R2") (pin "1") (pinfunction "1_1") (pintype "passive"))
      (node (ref "U4") (pin "3") (pinfunction "OUT_3") (pintype "power_in"))
      (node (ref "rECL") (pin "1") (pinfunction "1_1") (pintype "passive"))
    )
    (net (code "9") (name "5V_Iinv") (class "Default")
      (node (ref "C15") (pin "1") (pinfunction "1_1") (pintype "passive"))
      (node (ref "C16") (pin "2") (pinfunction "A_2") (pintype "passive"))
      (node (ref "R4") (pin "1") (pinfunction "1_1") (pintype "passive"))
      (node (ref "U8") (pin "3") (pinfunction "OUT_3") (pintype "power_in"))
      (node (ref "rECN") (pin "1") (pinfunction "1_1") (pintype "passive"))
    )
    (net (code "10") (name "5V_VPV") (class "Default")
      (node (ref "C3") (pin "1") (pinfunction "1_1") (pintype "passive"))
      (node (ref "C4") (pin "2") (pinfunction "A_2") (pintype "passive"))
      (node (ref "R1") (pin "1") (pinfunction "1_1") (pintype "passive"))
      (node (ref "U2") (pin "3") (pinfunction "OUT_3") (pintype "power_in"))
      (node (ref "rECK") (pin "1") (pinfunction "1_1") (pintype "passive"))
    )
    (net (code "11") (name "DC_IPV") (class "Default")
      (node (ref "C5") (pin "1") (pinfunction "C_1") (pintype "passive"))
      (node (ref "C6") (pin "2") (pinfunction "2_2") (pintype "passive"))
      (node (ref "C7") (pin "2") (pinfunction "2_2") (pintype "passive"))
      (node (ref "C8") (pin "1") (pinfunction "C_1") (pintype "passive"))
      (node (ref "PowerB") (pin "1") (pinfunction "K_1") (pintype "passive"))
      (node (ref "U3") (pin "2") (pinfunction "A_2") (pintype "passive"))
      (node (ref "U4") (pin "4") (pinfunction "GND_4") (pintype "power_in"))
      (node (ref "rECL") (pin "2") (pinfunction "2_2") (pintype "passive"))
    )
    (net (code "12") (name "DC_VPV") (class "Default")
      (node (ref "C1") (pin "1") (pinfunction "C_1") (pintype "passive"))
      (node (ref "C2") (pin "2") (pinfunction "2_2") (pintype "passive"))
      (node (ref "C3") (pin "2") (pinfunction "2_2") (pintype "passive"))
      (node (ref "C4") (pin "1") (pinfunction "C_1") (pintype "passive"))
      (node (ref "PowerA") (pin "1") (pinfunction "K_1") (pintype "passive"))
      (node (ref "U1") (pin "2") (pinfunction "A_2") (pintype "passive"))
      (node (ref "U2") (pin "4") (pinfunction "GND_4") (pintype "power_in"))
      (node (ref "rECK") (pin "2") (pinfunction "2_2") (pintype "passive"))
    )
    (net (code "13") (name "GND_Grid") (class "Default")
      (node (ref "C25") (pin "1") (pinfunction "C_1") (pintype "passive"))
      (node (ref "C26") (pin "2") (pinfunction "2_2") (pintype "passive"))
      (node (ref "C27") (pin "2") (pinfunction "2_2") (pintype "passive"))
      (node (ref "C28") (pin "1") (pinfunction "C_1") (pintype "passive"))
      (node (ref "PowerG") (pin "1") (pinfunction "K_1") (pintype "passive"))
      (node (ref "U13") (pin "2") (pinfunction "A_2") (pintype "passive"))
      (node (ref "U14") (pin "4") (pinfunction "GND_4") (pintype "power_in"))
      (node (ref "rECQ") (pin "2") (pinfunction "2_2") (pintype "passive"))
    )
    (net (code "14") (name "GND_Grid_Ref") (class "Default")
      (node (ref "C33") (pin "1") (pinfunction "C_1") (pintype "passive"))
      (node (ref "C34") (pin "2") (pinfunction "2_2") (pintype "passive"))
      (node (ref "C35") (pin "2") (pinfunction "2_2") (pintype "passive"))
      (node (ref "C36") (pin "1") (pinfunction "C_1") (pintype "passive"))
      (node (ref "PowerI") (pin "1") (pinfunction "K_1") (pintype "passive"))
      (node (ref "U17") (pin "2") (pinfunction "A_2") (pintype "passive"))
      (node (ref "U18") (pin "4") (pinfunction "GND_4") (pintype "power_in"))
      (node (ref "rECS") (pin "2") (pinfunction "2_2") (pintype "passive"))
    )
    (net (code "15") (name "GND_IPV") (class "Default")
      (node (ref "C21") (pin "1") (pinfunction "C_1") (pintype "passive"))
      (node (ref "C22") (pin "2") (pinfunction "2_2") (pintype "passive"))
      (node (ref "C23") (pin "2") (pinfunction "2_2") (pintype "passive"))
      (node (ref "C24") (pin "1") (pinfunction "C_1") (pintype "passive"))
      (node (ref "PowerF") (pin "1") (pinfunction "K_1") (pintype "passive"))
      (node (ref "U11") (pin "2") (pinfunction "A_2") (pintype "passive"))
      (node (ref "U12") (pin "4") (pinfunction "GND_4") (pintype "power_in"))
      (node (ref "rECP") (pin "2") (pinfunction "2_2") (pintype "passive"))
    )
    (net (code "16") (name "GND_Iinv") (class "Default")
      (node (ref "C29") (pin "1") (pinfunction "C_1") (pintype "passive"))
      (node (ref "C30") (pin "2") (pinfunction "2_2") (pintype "passive"))
      (node (ref "C31") (pin "2") (pinfunction "2_2") (pintype "passive"))
      (node (ref "C32") (pin "1") (pinfunction "C_1") (pintype "passive"))
      (node (ref "PowerH") (pin "1") (pinfunction "K_1") (pintype "passive"))
      (node (ref "U15") (pin "2") (pinfunction "A_2") (pintype "passive"))
      (node (ref "U16") (pin "4") (pinfunction "GND_4") (pintype "power_in"))
      (node (ref "rECR") (pin "2") (pinfunction "2_2") (pintype "passive"))
    )
    (net (code "17") (name "GND_Iinv_Ref") (class "Default")
      (node (ref "C37") (pin "1") (pinfunction "C_1") (pintype "passive"))
      (node (ref "C38") (pin "2") (pinfunction "2_2") (pintype "passive"))
      (node (ref "C39") (pin "2") (pinfunction "2_2") (pintype "passive"))
      (node (ref "C40") (pin "1") (pinfunction "C_1") (pintype "passive"))
      (node (ref "PowerJ") (pin "1") (pinfunction "K_1") (pintype "passive"))
      (node (ref "U19") (pin "2") (pinfunction "A_2") (pintype "passive"))
      (node (ref "U20") (pin "4") (pinfunction "GND_4") (pintype "power_in"))
      (node (ref "rECT") (pin "2") (pinfunction "2_2") (pintype "passive"))
    )
    (net (code "18") (name "GND_VPV") (class "Default")
      (node (ref "C17") (pin "1") (pinfunction "C_1") (pintype "passive"))
      (node (ref "C18") (pin "2") (pinfunction "2_2") (pintype "passive"))
      (node (ref "C19") (pin "2") (pinfunction "2_2") (pintype "passive"))
      (node (ref "C20") (pin "1") (pinfunction "C_1") (pintype "passive"))
      (node (ref "PowerE") (pin "1") (pinfunction "K_1") (pintype "passive"))
      (node (ref "U10") (pin "4") (pinfunction "GND_4") (pintype "power_in"))
      (node (ref "U9") (pin "2") (pinfunction "A_2") (pintype "passive"))
      (node (ref "rECO") (pin "2") (pinfunction "2_2") (pintype "passive"))
    )
    (net (code "19") (name "Net-(C1-A)") (class "Default")
      (node (ref "C1") (pin "2") (pinfunction "A_2") (pintype "passive"))
      (node (ref "C2") (pin "1") (pinfunction "1_1") (pintype "passive"))
      (node (ref "U1") (pin "1") (pinfunction "K_1") (pintype "passive"))
      (node (ref "U2") (pin "1") (pinfunction "IN_1") (pintype "power_in"))
    )
    (net (code "20") (name "Net-(C5-A)") (class "Default")
      (node (ref "C5") (pin "2") (pinfunction "A_2") (pintype "passive"))
      (node (ref "C6") (pin "1") (pinfunction "1_1") (pintype "passive"))
      (node (ref "U3") (pin "1") (pinfunction "K_1") (pintype "passive"))
      (node (ref "U4") (pin "1") (pinfunction "IN_1") (pintype "power_in"))
    )
    (net (code "21") (name "Net-(C9-A)") (class "Default")
      (node (ref "C10") (pin "1") (pinfunction "1_1") (pintype "passive"))
      (node (ref "C9") (pin "2") (pinfunction "A_2") (pintype "passive"))
      (node (ref "U5") (pin "1") (pinfunction "K_1") (pintype "passive"))
      (node (ref "U6") (pin "1") (pinfunction "IN_1") (pintype "power_in"))
    )
    (net (code "22") (name "Net-(C13-A)") (class "Default")
      (node (ref "C13") (pin "2") (pinfunction "A_2") (pintype "passive"))
      (node (ref "C14") (pin "1") (pinfunction "1_1") (pintype "passive"))
      (node (ref "U7") (pin "1") (pinfunction "K_1") (pintype "passive"))
      (node (ref "U8") (pin "1") (pinfunction "IN_1") (pintype "power_in"))
    )
    (net (code "23") (name "Net-(C17-A)") (class "Default")
      (node (ref "C17") (pin "2") (pinfunction "A_2") (pintype "passive"))
      (node (ref "C18") (pin "1") (pinfunction "1_1") (pintype "passive"))
      (node (ref "U10") (pin "1") (pinfunction "IN_1") (pintype "power_in"))
      (node (ref "U9") (pin "1") (pinfunction "K_1") (pintype "passive"))
    )
    (net (code "24") (name "Net-(C21-A)") (class "Default")
      (node (ref "C21") (pin "2") (pinfunction "A_2") (pintype "passive"))
      (node (ref "C22") (pin "1") (pinfunction "1_1") (pintype "passive"))
      (node (ref "U11") (pin "1") (pinfunction "K_1") (pintype "passive"))
      (node (ref "U12") (pin "1") (pinfunction "IN_1") (pintype "power_in"))
    )
    (net (code "25") (name "Net-(C25-A)") (class "Default")
      (node (ref "C25") (pin "2") (pinfunction "A_2") (pintype "passive"))
      (node (ref "C26") (pin "1") (pinfunction "1_1") (pintype "passive"))
      (node (ref "U13") (pin "1") (pinfunction "K_1") (pintype "passive"))
      (node (ref "U14") (pin "1") (pinfunction "IN_1") (pintype "power_in"))
    )
    (net (code "26") (name "Net-(C29-A)") (class "Default")
      (node (ref "C29") (pin "2") (pinfunction "A_2") (pintype "passive"))
      (node (ref "C30") (pin "1") (pinfunction "1_1") (pintype "passive"))
      (node (ref "U15") (pin "1") (pinfunction "K_1") (pintype "passive"))
      (node (ref "U16") (pin "1") (pinfunction "IN_1") (pintype "power_in"))
    )
    (net (code "27") (name "Net-(C33-A)") (class "Default")
      (node (ref "C33") (pin "2") (pinfunction "A_2") (pintype "passive"))
      (node (ref "C34") (pin "1") (pinfunction "1_1") (pintype "passive"))
      (node (ref "U17") (pin "1") (pinfunction "K_1") (pintype "passive"))
      (node (ref "U18") (pin "1") (pinfunction "IN_1") (pintype "power_in"))
    )
    (net (code "28") (name "Net-(C37-A)") (class "Default")
      (node (ref "C37") (pin "2") (pinfunction "A_2") (pintype "passive"))
      (node (ref "C38") (pin "1") (pinfunction "1_1") (pintype "passive"))
      (node (ref "U19") (pin "1") (pinfunction "K_1") (pintype "passive"))
      (node (ref "U20") (pin "1") (pinfunction "IN_1") (pintype "power_in"))
    )
    (net (code "29") (name "Net-(PowerA-A)") (class "Default")
      (node (ref "PowerA") (pin "2") (pinfunction "A_2") (pintype "passive"))
      (node (ref "R1") (pin "2") (pinfunction "2_2") (pintype "passive"))
    )
    (net (code "30") (name "Net-(PowerB-A)") (class "Default")
      (node (ref "PowerB") (pin "2") (pinfunction "A_2") (pintype "passive"))
      (node (ref "R2") (pin "2") (pinfunction "2_2") (pintype "passive"))
    )
    (net (code "31") (name "Net-(PowerC-A)") (class "Default")
      (node (ref "PowerC") (pin "2") (pinfunction "A_2") (pintype "passive"))
      (node (ref "R3") (pin "2") (pinfunction "2_2") (pintype "passive"))
    )
    (net (code "32") (name "Net-(PowerD-A)") (class "Default")
      (node (ref "PowerD") (pin "2") (pinfunction "A_2") (pintype "passive"))
      (node (ref "R4") (pin "2") (pinfunction "2_2") (pintype "passive"))
    )
    (net (code "33") (name "Net-(PowerE-A)") (class "Default")
      (node (ref "PowerE") (pin "2") (pinfunction "A_2") (pintype "passive"))
      (node (ref "R5") (pin "2") (pinfunction "2_2") (pintype "passive"))
    )
    (net (code "34") (name "Net-(PowerF-A)") (class "Default")
      (node (ref "PowerF") (pin "2") (pinfunction "A_2") (pintype "passive"))
      (node (ref "R6") (pin "2") (pinfunction "2_2") (pintype "passive"))
    )
    (net (code "35") (name "Net-(PowerG-A)") (class "Default")
      (node (ref "PowerG") (pin "2") (pinfunction "A_2") (pintype "passive"))
      (node (ref "R7") (pin "2") (pinfunction "2_2") (pintype "passive"))
    )
    (net (code "36") (name "Net-(PowerH-A)") (class "Default")
      (node (ref "PowerH") (pin "2") (pinfunction "A_2") (pintype "passive"))
      (node (ref "R8") (pin "2") (pinfunction "2_2") (pintype "passive"))
    )
    (net (code "37") (name "Net-(PowerI-A)") (class "Default")
      (node (ref "PowerI") (pin "2") (pinfunction "A_2") (pintype "passive"))
      (node (ref "R9") (pin "2") (pinfunction "2_2") (pintype "passive"))
    )
    (net (code "38") (name "Net-(PowerJ-A)") (class "Default")
      (node (ref "PowerJ") (pin "2") (pinfunction "A_2") (pintype "passive"))
      (node (ref "R10") (pin "2") (pinfunction "2_2") (pintype "passive"))
    )
    (net (code "39") (name "U_G") (class "Default")
      (node (ref "C13") (pin "1") (pinfunction "C_1") (pintype "passive"))
      (node (ref "C14") (pin "2") (pinfunction "2_2") (pintype "passive"))
      (node (ref "C15") (pin "2") (pinfunction "2_2") (pintype "passive"))
      (node (ref "C16") (pin "1") (pinfunction "C_1") (pintype "passive"))
      (node (ref "PowerD") (pin "1") (pinfunction "K_1") (pintype "passive"))
      (node (ref "U7") (pin "2") (pinfunction "A_2") (pintype "passive"))
      (node (ref "U8") (pin "4") (pinfunction "GND_4") (pintype "power_in"))
      (node (ref "rECN") (pin "2") (pinfunction "2_2") (pintype "passive"))
    )
    (net (code "40") (name "V_G") (class "Default")
      (node (ref "C10") (pin "2") (pinfunction "2_2") (pintype "passive"))
      (node (ref "C11") (pin "2") (pinfunction "2_2") (pintype "passive"))
      (node (ref "C12") (pin "1") (pinfunction "C_1") (pintype "passive"))
      (node (ref "C9") (pin "1") (pinfunction "C_1") (pintype "passive"))
      (node (ref "PowerC") (pin "1") (pinfunction "K_1") (pintype "passive"))
      (node (ref "U5") (pin "2") (pinfunction "A_2") (pintype "passive"))
      (node (ref "U6") (pin "4") (pinfunction "GND_4") (pintype "power_in"))
      (node (ref "rECM") (pin "2") (pinfunction "2_2") (pintype "passive"))
    )
    (net (code "41") (name "rECA_N") (class "Default")
      (node (ref "U1") (pin "4") (pinfunction "C_4") (pintype "passive"))
      (node (ref "rECA") (pin "2") (pinfunction "2_2") (pintype "passive"))
    )
    (net (code "42") (name "rECA_P") (class "Default")
      (node (ref "U1") (pin "3") (pinfunction "C_3") (pintype "passive"))
      (node (ref "rECA") (pin "1") (pinfunction "1_1") (pintype "passive"))
    )
    (net (code "43") (name "rECB_N") (class "Default")
      (node (ref "U3") (pin "4") (pinfunction "C_4") (pintype "passive"))
      (node (ref "rECB") (pin "2") (pinfunction "2_2") (pintype "passive"))
    )
    (net (code "44") (name "rECB_P") (class "Default")
      (node (ref "U3") (pin "3") (pinfunction "C_3") (pintype "passive"))
      (node (ref "rECB") (pin "1") (pinfunction "1_1") (pintype "passive"))
    )
    (net (code "45") (name "rECC_N") (class "Default")
      (node (ref "U5") (pin "4") (pinfunction "C_4") (pintype "passive"))
      (node (ref "rECC") (pin "2") (pinfunction "2_2") (pintype "passive"))
    )
    (net (code "46") (name "rECC_P") (class "Default")
      (node (ref "U5") (pin "3") (pinfunction "C_3") (pintype "passive"))
      (node (ref "rECC") (pin "1") (pinfunction "1_1") (pintype "passive"))
    )
    (net (code "47") (name "rECD_N") (class "Default")
      (node (ref "U7") (pin "4") (pinfunction "C_4") (pintype "passive"))
      (node (ref "rECD") (pin "2") (pinfunction "2_2") (pintype "passive"))
    )
    (net (code "48") (name "rECD_P") (class "Default")
      (node (ref "U7") (pin "3") (pinfunction "C_3") (pintype "passive"))
      (node (ref "rECD") (pin "1") (pinfunction "1_1") (pintype "passive"))
    )
    (net (code "49") (name "rECE_N") (class "Default")
      (node (ref "U9") (pin "4") (pinfunction "C_4") (pintype "passive"))
      (node (ref "rECE") (pin "2") (pinfunction "2_2") (pintype "passive"))
    )
    (net (code "50") (name "rECE_P") (class "Default")
      (node (ref "U9") (pin "3") (pinfunction "C_3") (pintype "passive"))
      (node (ref "rECE") (pin "1") (pinfunction "1_1") (pintype "passive"))
    )
    (net (code "51") (name "rECF_N") (class "Default")
      (node (ref "U11") (pin "4") (pinfunction "C_4") (pintype "passive"))
      (node (ref "rECF") (pin "2") (pinfunction "2_2") (pintype "passive"))
    )
    (net (code "52") (name "rECF_P") (class "Default")
      (node (ref "U11") (pin "3") (pinfunction "C_3") (pintype "passive"))
      (node (ref "rECF") (pin "1") (pinfunction "1_1") (pintype "passive"))
    )
    (net (code "53") (name "rECG_N") (class "Default")
      (node (ref "U13") (pin "4") (pinfunction "C_4") (pintype "passive"))
      (node (ref "rECG") (pin "2") (pinfunction "2_2") (pintype "passive"))
    )
    (net (code "54") (name "rECG_P") (class "Default")
      (node (ref "U13") (pin "3") (pinfunction "C_3") (pintype "passive"))
      (node (ref "rECG") (pin "1") (pinfunction "1_1") (pintype "passive"))
    )
    (net (code "55") (name "rECH_N") (class "Default")
      (node (ref "U15") (pin "4") (pinfunction "C_4") (pintype "passive"))
      (node (ref "rECH") (pin "2") (pinfunction "2_2") (pintype "passive"))
    )
    (net (code "56") (name "rECH_P") (class "Default")
      (node (ref "U15") (pin "3") (pinfunction "C_3") (pintype "passive"))
      (node (ref "rECH") (pin "1") (pinfunction "1_1") (pintype "passive"))
    )
    (net (code "57") (name "rECI_N") (class "Default")
      (node (ref "U17") (pin "4") (pinfunction "C_4") (pintype "passive"))
      (node (ref "rECI") (pin "2") (pinfunction "2_2") (pintype "passive"))
    )
    (net (code "58") (name "rECI_P") (class "Default")
      (node (ref "U17") (pin "3") (pinfunction "C_3") (pintype "passive"))
      (node (ref "rECI") (pin "1") (pinfunction "1_1") (pintype "passive"))
    )
    (net (code "59") (name "rECJ_N") (class "Default")
      (node (ref "U19") (pin "4") (pinfunction "C_4") (pintype "passive"))
      (node (ref "rECJ") (pin "2") (pinfunction "2_2") (pintype "passive"))
    )
    (net (code "60") (name "rECJ_P") (class "Default")
      (node (ref "U19") (pin "3") (pinfunction "C_3") (pintype "passive"))
      (node (ref "rECJ") (pin "1") (pinfunction "1_1") (pintype "passive"))
    )
  )
)
